# RMII_Ethernet.net
KiCad netlist of a schematic drawn in Altium Designer
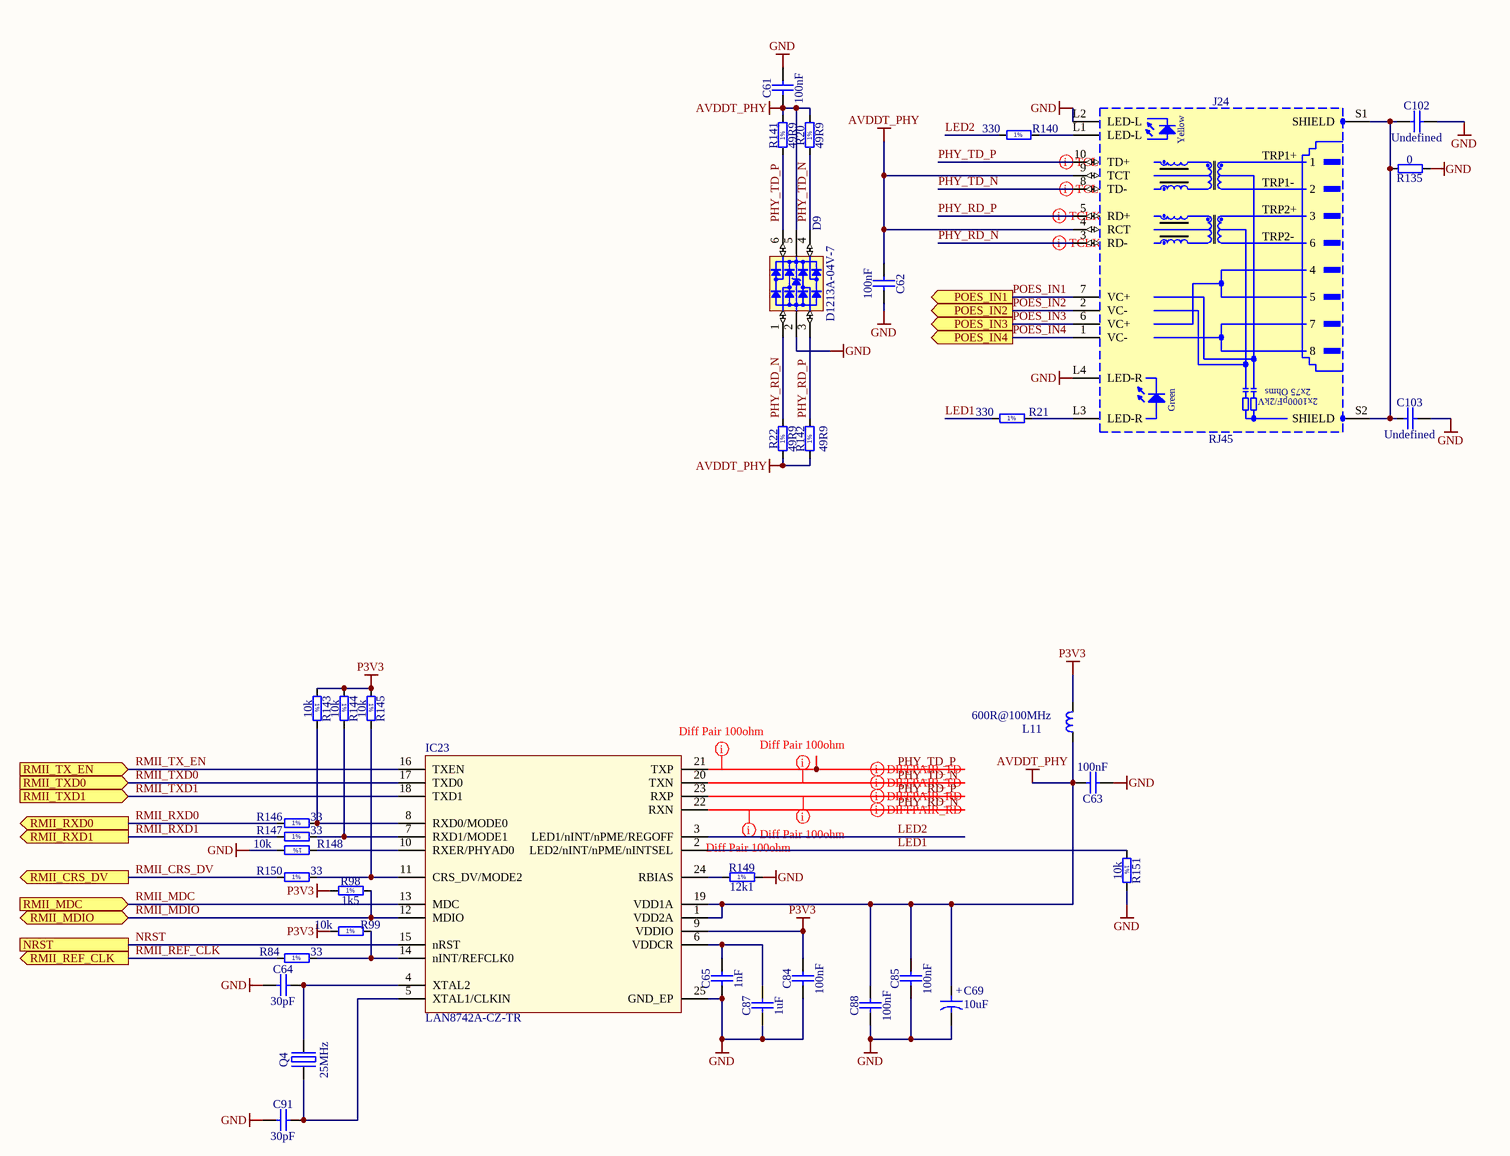
[diagram p0: RMII_Ethernet.SchDoc]

(export (version "E")
  (design (tool "Eeschema 10.0.6"))
  (components
    (comp (ref "C61")
      (value "100nF")
      (footprint "CAPC1005X55N")
      (description "Non-polarised capacitor")
      (fields
        (field (name "PART NUMBER") "CC0402_100NF_16V_10%_X7R")
        (field (name "VOLTAGE") "16V")
        (field (name "AUTHOR") "CERN DEM JLC")
      )
      (libsource (lib "Capacitors") (part "Capacitor - non polarized"))
    )
    (comp (ref "C62")
      (value "100nF")
      (footprint "CAPC1005X55N")
      (description "Non-polarised capacitor")
      (fields
        (field (name "PART NUMBER") "CC0402_100NF_16V_10%_X7R")
        (field (name "VOLTAGE") "16V")
        (field (name "AUTHOR") "CERN DEM JLC")
      )
      (libsource (lib "Capacitors") (part "Capacitor - non polarized"))
    )
    (comp (ref "C63")
      (value "100nF")
      (footprint "CAPC1005X55N")
      (description "Non-polarised capacitor")
      (fields
        (field (name "PART NUMBER") "CC0402_100NF_16V_10%_X7R")
        (field (name "VOLTAGE") "16V")
        (field (name "AUTHOR") "CERN DEM JLC")
      )
      (libsource (lib "Capacitors") (part "Capacitor - non polarized"))
    )
    (comp (ref "C64")
      (value "30pF")
      (footprint "CAPC1005X55N")
      (description "Non-polarised capacitor")
      (fields
        (field (name "PART NUMBER") "CC0402_30PF_50V_1%_C0G_MURATA_GJM1555C1H300FB01")
        (field (name "VOLTAGE") "50V")
        (field (name "AUTHOR") "CERN DEM BC")
      )
      (libsource (lib "Capacitors") (part "Capacitor - non polarized"))
    )
    (comp (ref "C65")
      (value "1nF")
      (footprint "CAPC1608X87N")
      (description "Non-polarised capacitor")
      (fields
        (field (name "PART NUMBER") "CC0603_1NF_100V_10%_X7R")
        (field (name "VOLTAGE") "100V")
        (field (name "AUTHOR") "CERN DEM JLC")
      )
      (libsource (lib "Capacitors") (part "Capacitor - non polarized"))
    )
    (comp (ref "C69")
      (value "10uF")
      (footprint "CAPMP3216X180N")
      (description "Polarised capacitor")
      (fields
        (field (name "PART NUMBER") "CTE3216-18_10UF_16V_20%_AVX_TCJ")
        (field (name "VOLTAGE") "16V")
        (field (name "AUTHOR") "CERN DEM JLC")
      )
      (libsource (lib "Capacitors") (part "Capacitor - polarized"))
    )
    (comp (ref "C84")
      (value "100nF")
      (footprint "CAPC1005X55N")
      (description "Non-polarised capacitor")
      (fields
        (field (name "PART NUMBER") "CC0402_100NF_16V_10%_X7R")
        (field (name "VOLTAGE") "16V")
        (field (name "AUTHOR") "CERN DEM JLC")
      )
      (libsource (lib "Capacitors") (part "Capacitor - non polarized"))
    )
    (comp (ref "C85")
      (value "100nF")
      (footprint "CAPC1005X55N")
      (description "Non-polarised capacitor")
      (fields
        (field (name "PART NUMBER") "CC0402_100NF_16V_10%_X7R")
        (field (name "VOLTAGE") "16V")
        (field (name "AUTHOR") "CERN DEM JLC")
      )
      (libsource (lib "Capacitors") (part "Capacitor - non polarized"))
    )
    (comp (ref "C87")
      (value "1uF")
      (footprint "CAPC1608X87N")
      (description "Non-polarised capacitor")
      (fields
        (field (name "PART NUMBER") "CC0603_1UF_16V_10%_X7R")
        (field (name "VOLTAGE") "16V")
        (field (name "AUTHOR") "CERN DEM JLC")
      )
      (libsource (lib "Capacitors") (part "Capacitor - non polarized"))
    )
    (comp (ref "C88")
      (value "100nF")
      (footprint "CAPC1005X55N")
      (description "Non-polarised capacitor")
      (fields
        (field (name "PART NUMBER") "CC0402_100NF_16V_10%_X7R")
        (field (name "VOLTAGE") "16V")
        (field (name "AUTHOR") "CERN DEM JLC")
      )
      (libsource (lib "Capacitors") (part "Capacitor - non polarized"))
    )
    (comp (ref "C91")
      (value "30pF")
      (footprint "CAPC1005X55N")
      (description "Non-polarised capacitor")
      (fields
        (field (name "PART NUMBER") "CC0402_30PF_50V_1%_C0G_MURATA_GJM1555C1H300FB01")
        (field (name "VOLTAGE") "50V")
        (field (name "AUTHOR") "CERN DEM BC")
      )
      (libsource (lib "Capacitors") (part "Capacitor - non polarized"))
    )
    (comp (ref "C102")
      (value "Undefined")
      (footprint "CAPC2012X135N")
      (description "Non-polarised capacitor")
      (fields (field (name "PART NUMBER") "CC0805_NO-VALUE") (field (name "AUTHOR") "CERN DEM JLC"))
      (libsource (lib "Capacitors") (part "Capacitor - non polarized"))
    )
    (comp (ref "C103")
      (value "Undefined")
      (footprint "CAPC2012X135N")
      (description "Non-polarised capacitor")
      (fields (field (name "PART NUMBER") "CC0805_NO-VALUE") (field (name "AUTHOR") "CERN DEM JLC"))
      (libsource (lib "Capacitors") (part "Capacitor - non polarized"))
    )
    (comp (ref "D9")
      (value "D1213A-04V-7")
      (footprint "SOTFL50P160X60-6N")
      (fields
        (field (name "VOLTAGE") "6V")
        (field (name "MANUFACTURER") "DIODES")
        (field (name "AUTHOR") "GK")
      )
      (libsource (lib "ICs And Semiconductors") (part "NUP4114"))
    )
    (comp (ref "IC23")
      (value "LAN8742A-CZ-TR")
      (footprint "QFN24_0R5_4X4")
      (libsource (lib "LIBRARY_SCH") (part "IFC_LAN8742A"))
    )
    (comp (ref "J24")
      (value "RJ45")
      (footprint "ABRACON_ARJM11C7-114-BA-EW2")
      (description "MagJack 10/100BaseT, PoE+, 1X1, OG/Y, -40 to 85*C, Tab Up, RoHS")
      (fields
        (field (name "PART NUMBER") "ARJM11C7-114-BA-EW2")
        (field (name "MANUFACTURER") "Abracon")
        (field (name "AUTHOR") "GK")
      )
      (libsource (lib "LIBRARY_SCH") (part "CON_ETH_POE_ARJM11C7"))
    )
    (comp (ref "L11")
      (value "600R@100MHz")
      (footprint "INDC1005X55N")
      (description "Inductor")
      (fields
        (field (name "PART NUMBER") "IND0402_MURATA_BLM15HD601SN1")
        (field (name "POWER") "300mA")
        (field (name "AUTHOR") "CERN DEM JLC")
      )
      (libsource (lib "Inductors & Transformers") (part "Inductor"))
    )
    (comp (ref "Q4")
      (value "25MHz")
      (footprint "XTAL_ABRACON_ABLS")
      (description "Quartz Crystal")
      (fields
        (field (name "PART NUMBER") "XTAL_25MHZ_ABRACON_ABLS-25.000MHZ-B2F-T")
        (field (name "MANUFACTURER") "ABRACON")
        (field (name "AUTHOR") "CERN DEM JLC")
      )
      (libsource (lib "ICs And Semiconductors") (part "Quartz Crystal"))
    )
    (comp (ref "R20")
      (value "49R9")
      (footprint "RESC1005X40N")
      (description "Resistor - 1%")
      (fields
        (field (name "PART NUMBER") "R0402_49R9_1%_0.0625W_100PPM")
        (field (name "POWER") "0.0625W")
        (field (name "AUTHOR") "CERN DEM JLC")
      )
      (libsource (lib "Resistors") (part "Resistor - 1%"))
    )
    (comp (ref "R21")
      (value "330")
      (footprint "RESC1005X40N")
      (description "Resistor - 1%")
      (fields
        (field (name "PART NUMBER") "R0402_330R_1%_0.0625W_100PPM")
        (field (name "POWER") "0.0625W")
        (field (name "AUTHOR") "CERN DEM JLC")
      )
      (libsource (lib "Resistors") (part "Resistor - 1%"))
    )
    (comp (ref "R22")
      (value "49R9")
      (footprint "RESC1005X40N")
      (description "Resistor - 1%")
      (fields
        (field (name "PART NUMBER") "R0402_49R9_1%_0.0625W_100PPM")
        (field (name "POWER") "0.0625W")
        (field (name "AUTHOR") "CERN DEM JLC")
      )
      (libsource (lib "Resistors") (part "Resistor - 1%"))
    )
    (comp (ref "R84")
      (value "33")
      (footprint "RESC1005X40N")
      (description "Resistor - 1%")
      (fields
        (field (name "PART NUMBER") "R0402_33R_1%_0.0625W_100PPM")
        (field (name "POWER") "0.0625W")
        (field (name "AUTHOR") "CERN DEM JLC")
      )
      (libsource (lib "Resistors") (part "Resistor - 1%"))
    )
    (comp (ref "R98")
      (value "1k5")
      (footprint "RESC1005X40N")
      (description "Resistor - 1%")
      (fields
        (field (name "PART NUMBER") "R0402_1K5_1%_0.0625W_100PPM")
        (field (name "POWER") "0.0625W")
        (field (name "AUTHOR") "CERN DEM JLC")
      )
      (libsource (lib "Resistors") (part "Resistor - 1%"))
    )
    (comp (ref "R99")
      (value "10k")
      (footprint "RESC1005X40N")
      (description "Resistor - 1%")
      (fields
        (field (name "PART NUMBER") "R0402_10K_1%_0.0625W_100PPM")
        (field (name "POWER") "0.0625W")
        (field (name "AUTHOR") "CERN DEM JLC")
      )
      (libsource (lib "Resistors") (part "Resistor - 1%"))
    )
    (comp (ref "R135")
      (value "0")
      (footprint "RESC1608X55N")
      (description "Resistor")
      (fields
        (field (name "PART NUMBER") "R0603_0R_JUMPER")
        (field (name "MANUFACTURER") "GENERIC")
        (field (name "AUTHOR") "CERN DEM JLC")
      )
      (libsource (lib "Resistors") (part "Resistor"))
    )
    (comp (ref "R140")
      (value "330")
      (footprint "RESC1005X40N")
      (description "Resistor - 1%")
      (fields
        (field (name "PART NUMBER") "R0402_330R_1%_0.0625W_100PPM")
        (field (name "POWER") "0.0625W")
        (field (name "AUTHOR") "CERN DEM JLC")
      )
      (libsource (lib "Resistors") (part "Resistor - 1%"))
    )
    (comp (ref "R141")
      (value "49R9")
      (footprint "RESC1005X40N")
      (description "Resistor - 1%")
      (fields
        (field (name "PART NUMBER") "R0402_49R9_1%_0.0625W_100PPM")
        (field (name "POWER") "0.0625W")
        (field (name "AUTHOR") "CERN DEM JLC")
      )
      (libsource (lib "Resistors") (part "Resistor - 1%"))
    )
    (comp (ref "R142")
      (value "49R9")
      (footprint "RESC1005X40N")
      (description "Resistor - 1%")
      (fields
        (field (name "PART NUMBER") "R0402_49R9_1%_0.0625W_100PPM")
        (field (name "POWER") "0.0625W")
        (field (name "AUTHOR") "CERN DEM JLC")
      )
      (libsource (lib "Resistors") (part "Resistor - 1%"))
    )
    (comp (ref "R143")
      (value "10k")
      (footprint "RESC1005X40N")
      (description "Resistor - 1%")
      (fields
        (field (name "PART NUMBER") "R0402_10K_1%_0.0625W_100PPM")
        (field (name "POWER") "0.0625W")
        (field (name "AUTHOR") "CERN DEM JLC")
      )
      (libsource (lib "Resistors") (part "Resistor - 1%"))
    )
    (comp (ref "R144")
      (value "10k")
      (footprint "RESC1005X40N")
      (description "Resistor - 1%")
      (fields
        (field (name "PART NUMBER") "R0402_10K_1%_0.0625W_100PPM")
        (field (name "POWER") "0.0625W")
        (field (name "AUTHOR") "CERN DEM JLC")
      )
      (libsource (lib "Resistors") (part "Resistor - 1%"))
    )
    (comp (ref "R145")
      (value "10k")
      (footprint "RESC1005X40N")
      (description "Resistor - 1%")
      (fields
        (field (name "PART NUMBER") "R0402_10K_1%_0.0625W_100PPM")
        (field (name "POWER") "0.0625W")
        (field (name "AUTHOR") "CERN DEM JLC")
      )
      (libsource (lib "Resistors") (part "Resistor - 1%"))
    )
    (comp (ref "R146")
      (value "33")
      (footprint "RESC1005X40N")
      (description "Resistor - 1%")
      (fields
        (field (name "PART NUMBER") "R0402_33R_1%_0.0625W_100PPM")
        (field (name "POWER") "0.0625W")
        (field (name "AUTHOR") "CERN DEM JLC")
      )
      (libsource (lib "Resistors") (part "Resistor - 1%"))
    )
    (comp (ref "R147")
      (value "33")
      (footprint "RESC1005X40N")
      (description "Resistor - 1%")
      (fields
        (field (name "PART NUMBER") "R0402_33R_1%_0.0625W_100PPM")
        (field (name "POWER") "0.0625W")
        (field (name "AUTHOR") "CERN DEM JLC")
      )
      (libsource (lib "Resistors") (part "Resistor - 1%"))
    )
    (comp (ref "R148")
      (value "10k")
      (footprint "RESC1005X40N")
      (description "Resistor - 1%")
      (fields
        (field (name "PART NUMBER") "R0402_10K_1%_0.0625W_100PPM")
        (field (name "POWER") "0.0625W")
        (field (name "AUTHOR") "CERN DEM JLC")
      )
      (libsource (lib "Resistors") (part "Resistor - 1%"))
    )
    (comp (ref "R149")
      (value "12k1")
      (footprint "RESC1005X40N")
      (description "Resistor - 1%")
      (fields
        (field (name "PART NUMBER") "R0402_12K1_1%_0.0625W_100PPM")
        (field (name "POWER") "0.0625W")
        (field (name "AUTHOR") "CERN DEM JLC")
      )
      (libsource (lib "Resistors") (part "Resistor - 1%"))
    )
    (comp (ref "R150")
      (value "33")
      (footprint "RESC1005X40N")
      (description "Resistor - 1%")
      (fields
        (field (name "PART NUMBER") "R0402_33R_1%_0.0625W_100PPM")
        (field (name "POWER") "0.0625W")
        (field (name "AUTHOR") "CERN DEM JLC")
      )
      (libsource (lib "Resistors") (part "Resistor - 1%"))
    )
    (comp (ref "R151")
      (value "10k")
      (footprint "RESC1005X40N")
      (description "Resistor - 1%")
      (fields
        (field (name "PART NUMBER") "R0402_10K_1%_0.0625W_100PPM")
        (field (name "POWER") "0.0625W")
        (field (name "AUTHOR") "CERN DEM JLC")
      )
      (libsource (lib "Resistors") (part "Resistor - 1%"))
    )
  )
  (nets
    (net (code "1") (name "/LED1") (class "Default")
      (node (ref "IC23") (pin "2") (pinfunction "LED2/nINT/nPME/nINTSEL_2") (pintype "passive"))
      (node (ref "R151") (pin "1") (pinfunction "1_1") (pintype "passive"))
      (node (ref "R21") (pin "1") (pinfunction "1_1") (pintype "passive"))
    )
    (net (code "2") (name "/LED2") (class "Default")
      (node (ref "IC23") (pin "3") (pinfunction "LED1/nINT/nPME/REGOFF_3") (pintype "passive"))
      (node (ref "R140") (pin "1") (pinfunction "1_1") (pintype "passive"))
    )
    (net (code "3") (name "/NRST") (class "Default")
      (node (ref "IC23") (pin "15") (pinfunction "nRST_15") (pintype "passive"))
    )
    (net (code "4") (name "/PHY_RD_N") (class "Default")
      (node (ref "D9") (pin "1") (pinfunction "I/O1_1") (pintype "bidirectional"))
      (node (ref "IC23") (pin "22") (pinfunction "RXN_22") (pintype "passive"))
      (node (ref "J24") (pin "3") (pinfunction "RD-_3") (pintype "bidirectional"))
      (node (ref "R22") (pin "2") (pinfunction "2_2") (pintype "passive"))
    )
    (net (code "5") (name "/PHY_RD_P") (class "Default")
      (node (ref "D9") (pin "3") (pinfunction "I/O2_3") (pintype "bidirectional"))
      (node (ref "IC23") (pin "23") (pinfunction "RXP_23") (pintype "passive"))
      (node (ref "J24") (pin "5") (pinfunction "RD+_5") (pintype "bidirectional"))
      (node (ref "R142") (pin "2") (pinfunction "2_2") (pintype "passive"))
    )
    (net (code "6") (name "/PHY_TD_N") (class "Default")
      (node (ref "D9") (pin "4") (pinfunction "I/O3_4") (pintype "bidirectional"))
      (node (ref "IC23") (pin "20") (pinfunction "TXN_20") (pintype "passive"))
      (node (ref "J24") (pin "8") (pinfunction "TD-_8") (pintype "bidirectional"))
      (node (ref "R20") (pin "1") (pinfunction "1_1") (pintype "passive"))
    )
    (net (code "7") (name "/PHY_TD_P") (class "Default")
      (node (ref "D9") (pin "6") (pinfunction "I/O4_6") (pintype "bidirectional"))
      (node (ref "IC23") (pin "21") (pinfunction "TXP_21") (pintype "passive"))
      (node (ref "J24") (pin "10") (pinfunction "TD+_10") (pintype "bidirectional"))
      (node (ref "R141") (pin "1") (pinfunction "1_1") (pintype "passive"))
    )
    (net (code "8") (name "/POES_IN1") (class "Default")
      (node (ref "J24") (pin "7") (pinfunction "VC+_7") (pintype "passive"))
    )
    (net (code "9") (name "/POES_IN2") (class "Default")
      (node (ref "J24") (pin "2") (pinfunction "VC-_2") (pintype "passive"))
    )
    (net (code "10") (name "/POES_IN3") (class "Default")
      (node (ref "J24") (pin "6") (pinfunction "VC+_6") (pintype "passive"))
    )
    (net (code "11") (name "/POES_IN4") (class "Default")
      (node (ref "J24") (pin "1") (pinfunction "VC-_1") (pintype "passive"))
    )
    (net (code "12") (name "/RMII_CRS_DV") (class "Default")
      (node (ref "R150") (pin "1") (pinfunction "1_1") (pintype "passive"))
    )
    (net (code "13") (name "/RMII_MDC") (class "Default")
      (node (ref "IC23") (pin "13") (pinfunction "MDC_13") (pintype "passive"))
    )
    (net (code "14") (name "/RMII_MDIO") (class "Default")
      (node (ref "IC23") (pin "12") (pinfunction "MDIO_12") (pintype "passive"))
      (node (ref "R98") (pin "2") (pinfunction "2_2") (pintype "passive"))
    )
    (net (code "15") (name "/RMII_REF_CLK") (class "Default")
      (node (ref "R84") (pin "1") (pinfunction "1_1") (pintype "passive"))
    )
    (net (code "16") (name "/RMII_RXD0") (class "Default")
      (node (ref "R146") (pin "1") (pinfunction "1_1") (pintype "passive"))
    )
    (net (code "17") (name "/RMII_RXD1") (class "Default")
      (node (ref "R147") (pin "1") (pinfunction "1_1") (pintype "passive"))
    )
    (net (code "18") (name "/RMII_TXD0") (class "Default")
      (node (ref "IC23") (pin "17") (pinfunction "TXD0_17") (pintype "passive"))
    )
    (net (code "19") (name "/RMII_TXD1") (class "Default")
      (node (ref "IC23") (pin "18") (pinfunction "TXD1_18") (pintype "passive"))
    )
    (net (code "20") (name "/RMII_TX_EN") (class "Default")
      (node (ref "IC23") (pin "16") (pinfunction "TXEN_16") (pintype "passive"))
    )
    (net (code "21") (name "AVDDT_PHY") (class "Default")
      (node (ref "C61") (pin "1") (pinfunction "1_1") (pintype "passive"))
      (node (ref "C62") (pin "2") (pinfunction "2_2") (pintype "passive"))
      (node (ref "C63") (pin "2") (pinfunction "2_2") (pintype "passive"))
      (node (ref "C69") (pin "1") (pinfunction "1_1") (pintype "passive"))
      (node (ref "C85") (pin "2") (pinfunction "2_2") (pintype "passive"))
      (node (ref "C88") (pin "2") (pinfunction "2_2") (pintype "passive"))
      (node (ref "D9") (pin "5") (pinfunction "VBUS_5") (pintype "power_in"))
      (node (ref "IC23") (pin "1") (pinfunction "VDD2A_1") (pintype "passive"))
      (node (ref "IC23") (pin "19") (pinfunction "VDD1A_19") (pintype "passive"))
      (node (ref "J24") (pin "4") (pinfunction "RCT_4") (pintype "bidirectional"))
      (node (ref "J24") (pin "9") (pinfunction "TCT_9") (pintype "bidirectional"))
      (node (ref "L11") (pin "1") (pinfunction "1_1") (pintype "passive"))
      (node (ref "R141") (pin "2") (pinfunction "2_2") (pintype "passive"))
      (node (ref "R142") (pin "1") (pinfunction "1_1") (pintype "passive"))
      (node (ref "R20") (pin "2") (pinfunction "2_2") (pintype "passive"))
      (node (ref "R22") (pin "1") (pinfunction "1_1") (pintype "passive"))
    )
    (net (code "22") (name "GND") (class "Default")
      (node (ref "C102") (pin "2") (pinfunction "2_2") (pintype "passive"))
      (node (ref "C103") (pin "2") (pinfunction "2_2") (pintype "passive"))
      (node (ref "C61") (pin "2") (pinfunction "2_2") (pintype "passive"))
      (node (ref "C62") (pin "1") (pinfunction "1_1") (pintype "passive"))
      (node (ref "C63") (pin "1") (pinfunction "1_1") (pintype "passive"))
      (node (ref "C64") (pin "1") (pinfunction "1_1") (pintype "passive"))
      (node (ref "C65") (pin "1") (pinfunction "1_1") (pintype "passive"))
      (node (ref "C69") (pin "2") (pinfunction "2_2") (pintype "passive"))
      (node (ref "C84") (pin "1") (pinfunction "1_1") (pintype "passive"))
      (node (ref "C85") (pin "1") (pinfunction "1_1") (pintype "passive"))
      (node (ref "C87") (pin "1") (pinfunction "1_1") (pintype "passive"))
      (node (ref "C88") (pin "1") (pinfunction "1_1") (pintype "passive"))
      (node (ref "C91") (pin "1") (pinfunction "1_1") (pintype "passive"))
      (node (ref "D9") (pin "2") (pinfunction "GND_2") (pintype "power_in"))
      (node (ref "IC23") (pin "25") (pinfunction "GND_EP_25") (pintype "passive"))
      (node (ref "J24") (pin "L2") (pinfunction "LED-L_L2") (pintype "passive"))
      (node (ref "J24") (pin "L4") (pinfunction "LED-R_L4") (pintype "passive"))
      (node (ref "R135") (pin "1") (pinfunction "1_1") (pintype "passive"))
      (node (ref "R148") (pin "2") (pinfunction "2_2") (pintype "passive"))
      (node (ref "R149") (pin "2") (pinfunction "2_2") (pintype "passive"))
      (node (ref "R151") (pin "2") (pinfunction "2_2") (pintype "passive"))
    )
    (net (code "23") (name "Net-(C102-Pad1)") (class "Default")
      (node (ref "C102") (pin "1") (pinfunction "1_1") (pintype "passive"))
      (node (ref "C103") (pin "1") (pinfunction "1_1") (pintype "passive"))
      (node (ref "J24") (pin "S1") (pinfunction "SHIELD_S1") (pintype "power_in"))
      (node (ref "J24") (pin "S2") (pinfunction "SHIELD_S2") (pintype "power_in"))
      (node (ref "R135") (pin "2") (pinfunction "2_2") (pintype "passive"))
    )
    (net (code "24") (name "Net-(IC23-CRS_DV{slash}MODE2)") (class "Default")
      (node (ref "IC23") (pin "11") (pinfunction "CRS_DV/MODE2_11") (pintype "passive"))
      (node (ref "R145") (pin "2") (pinfunction "2_2") (pintype "passive"))
      (node (ref "R150") (pin "2") (pinfunction "2_2") (pintype "passive"))
    )
    (net (code "25") (name "Net-(IC23-RBIAS)") (class "Default")
      (node (ref "IC23") (pin "24") (pinfunction "RBIAS_24") (pintype "passive"))
      (node (ref "R149") (pin "1") (pinfunction "1_1") (pintype "passive"))
    )
    (net (code "26") (name "Net-(IC23-RXD0{slash}MODE0)") (class "Default")
      (node (ref "IC23") (pin "8") (pinfunction "RXD0/MODE0_8") (pintype "passive"))
      (node (ref "R143") (pin "2") (pinfunction "2_2") (pintype "passive"))
      (node (ref "R146") (pin "2") (pinfunction "2_2") (pintype "passive"))
    )
    (net (code "27") (name "Net-(IC23-RXD1{slash}MODE1)") (class "Default")
      (node (ref "IC23") (pin "7") (pinfunction "RXD1/MODE1_7") (pintype "passive"))
      (node (ref "R144") (pin "2") (pinfunction "2_2") (pintype "passive"))
      (node (ref "R147") (pin "2") (pinfunction "2_2") (pintype "passive"))
    )
    (net (code "28") (name "Net-(IC23-RXER{slash}PHYAD0)") (class "Default")
      (node (ref "IC23") (pin "10") (pinfunction "RXER/PHYAD0_10") (pintype "passive"))
      (node (ref "R148") (pin "1") (pinfunction "1_1") (pintype "passive"))
    )
    (net (code "29") (name "Net-(IC23-VDDCR)") (class "Default")
      (node (ref "C65") (pin "2") (pinfunction "2_2") (pintype "passive"))
      (node (ref "C87") (pin "2") (pinfunction "2_2") (pintype "passive"))
      (node (ref "IC23") (pin "6") (pinfunction "VDDCR_6") (pintype "passive"))
    )
    (net (code "30") (name "Net-(IC23-XTAL1{slash}CLKIN)") (class "Default")
      (node (ref "C91") (pin "2") (pinfunction "2_2") (pintype "passive"))
      (node (ref "IC23") (pin "5") (pinfunction "XTAL1/CLKIN_5") (pintype "passive"))
      (node (ref "Q4") (pin "1") (pinfunction "OSC1_1") (pintype "passive"))
    )
    (net (code "31") (name "Net-(IC23-XTAL2)") (class "Default")
      (node (ref "C64") (pin "2") (pinfunction "2_2") (pintype "passive"))
      (node (ref "IC23") (pin "4") (pinfunction "XTAL2_4") (pintype "passive"))
      (node (ref "Q4") (pin "2") (pinfunction "OSC2_2") (pintype "passive"))
    )
    (net (code "32") (name "Net-(IC23-nINT{slash}REFCLK0)") (class "Default")
      (node (ref "IC23") (pin "14") (pinfunction "nINT/REFCLK0_14") (pintype "passive"))
      (node (ref "R84") (pin "2") (pinfunction "2_2") (pintype "passive"))
      (node (ref "R99") (pin "2") (pinfunction "2_2") (pintype "passive"))
    )
    (net (code "33") (name "Net-(J24-LED-L-PadL1)") (class "Default")
      (node (ref "J24") (pin "L1") (pinfunction "LED-L_L1") (pintype "passive"))
      (node (ref "R140") (pin "2") (pinfunction "2_2") (pintype "passive"))
    )
    (net (code "34") (name "Net-(J24-LED-R-PadL3)") (class "Default")
      (node (ref "J24") (pin "L3") (pinfunction "LED-R_L3") (pintype "passive"))
      (node (ref "R21") (pin "2") (pinfunction "2_2") (pintype "passive"))
    )
    (net (code "35") (name "P3V3") (class "Default")
      (node (ref "C84") (pin "2") (pinfunction "2_2") (pintype "passive"))
      (node (ref "IC23") (pin "9") (pinfunction "VDDIO_9") (pintype "passive"))
      (node (ref "L11") (pin "2") (pinfunction "2_2") (pintype "passive"))
      (node (ref "R143") (pin "1") (pinfunction "1_1") (pintype "passive"))
      (node (ref "R144") (pin "1") (pinfunction "1_1") (pintype "passive"))
      (node (ref "R145") (pin "1") (pinfunction "1_1") (pintype "passive"))
      (node (ref "R98") (pin "1") (pinfunction "1_1") (pintype "passive"))
      (node (ref "R99") (pin "1") (pinfunction "1_1") (pintype "passive"))
    )
  )
)
